# precharge.net
KiCad netlist of a schematic drawn in EAGLE
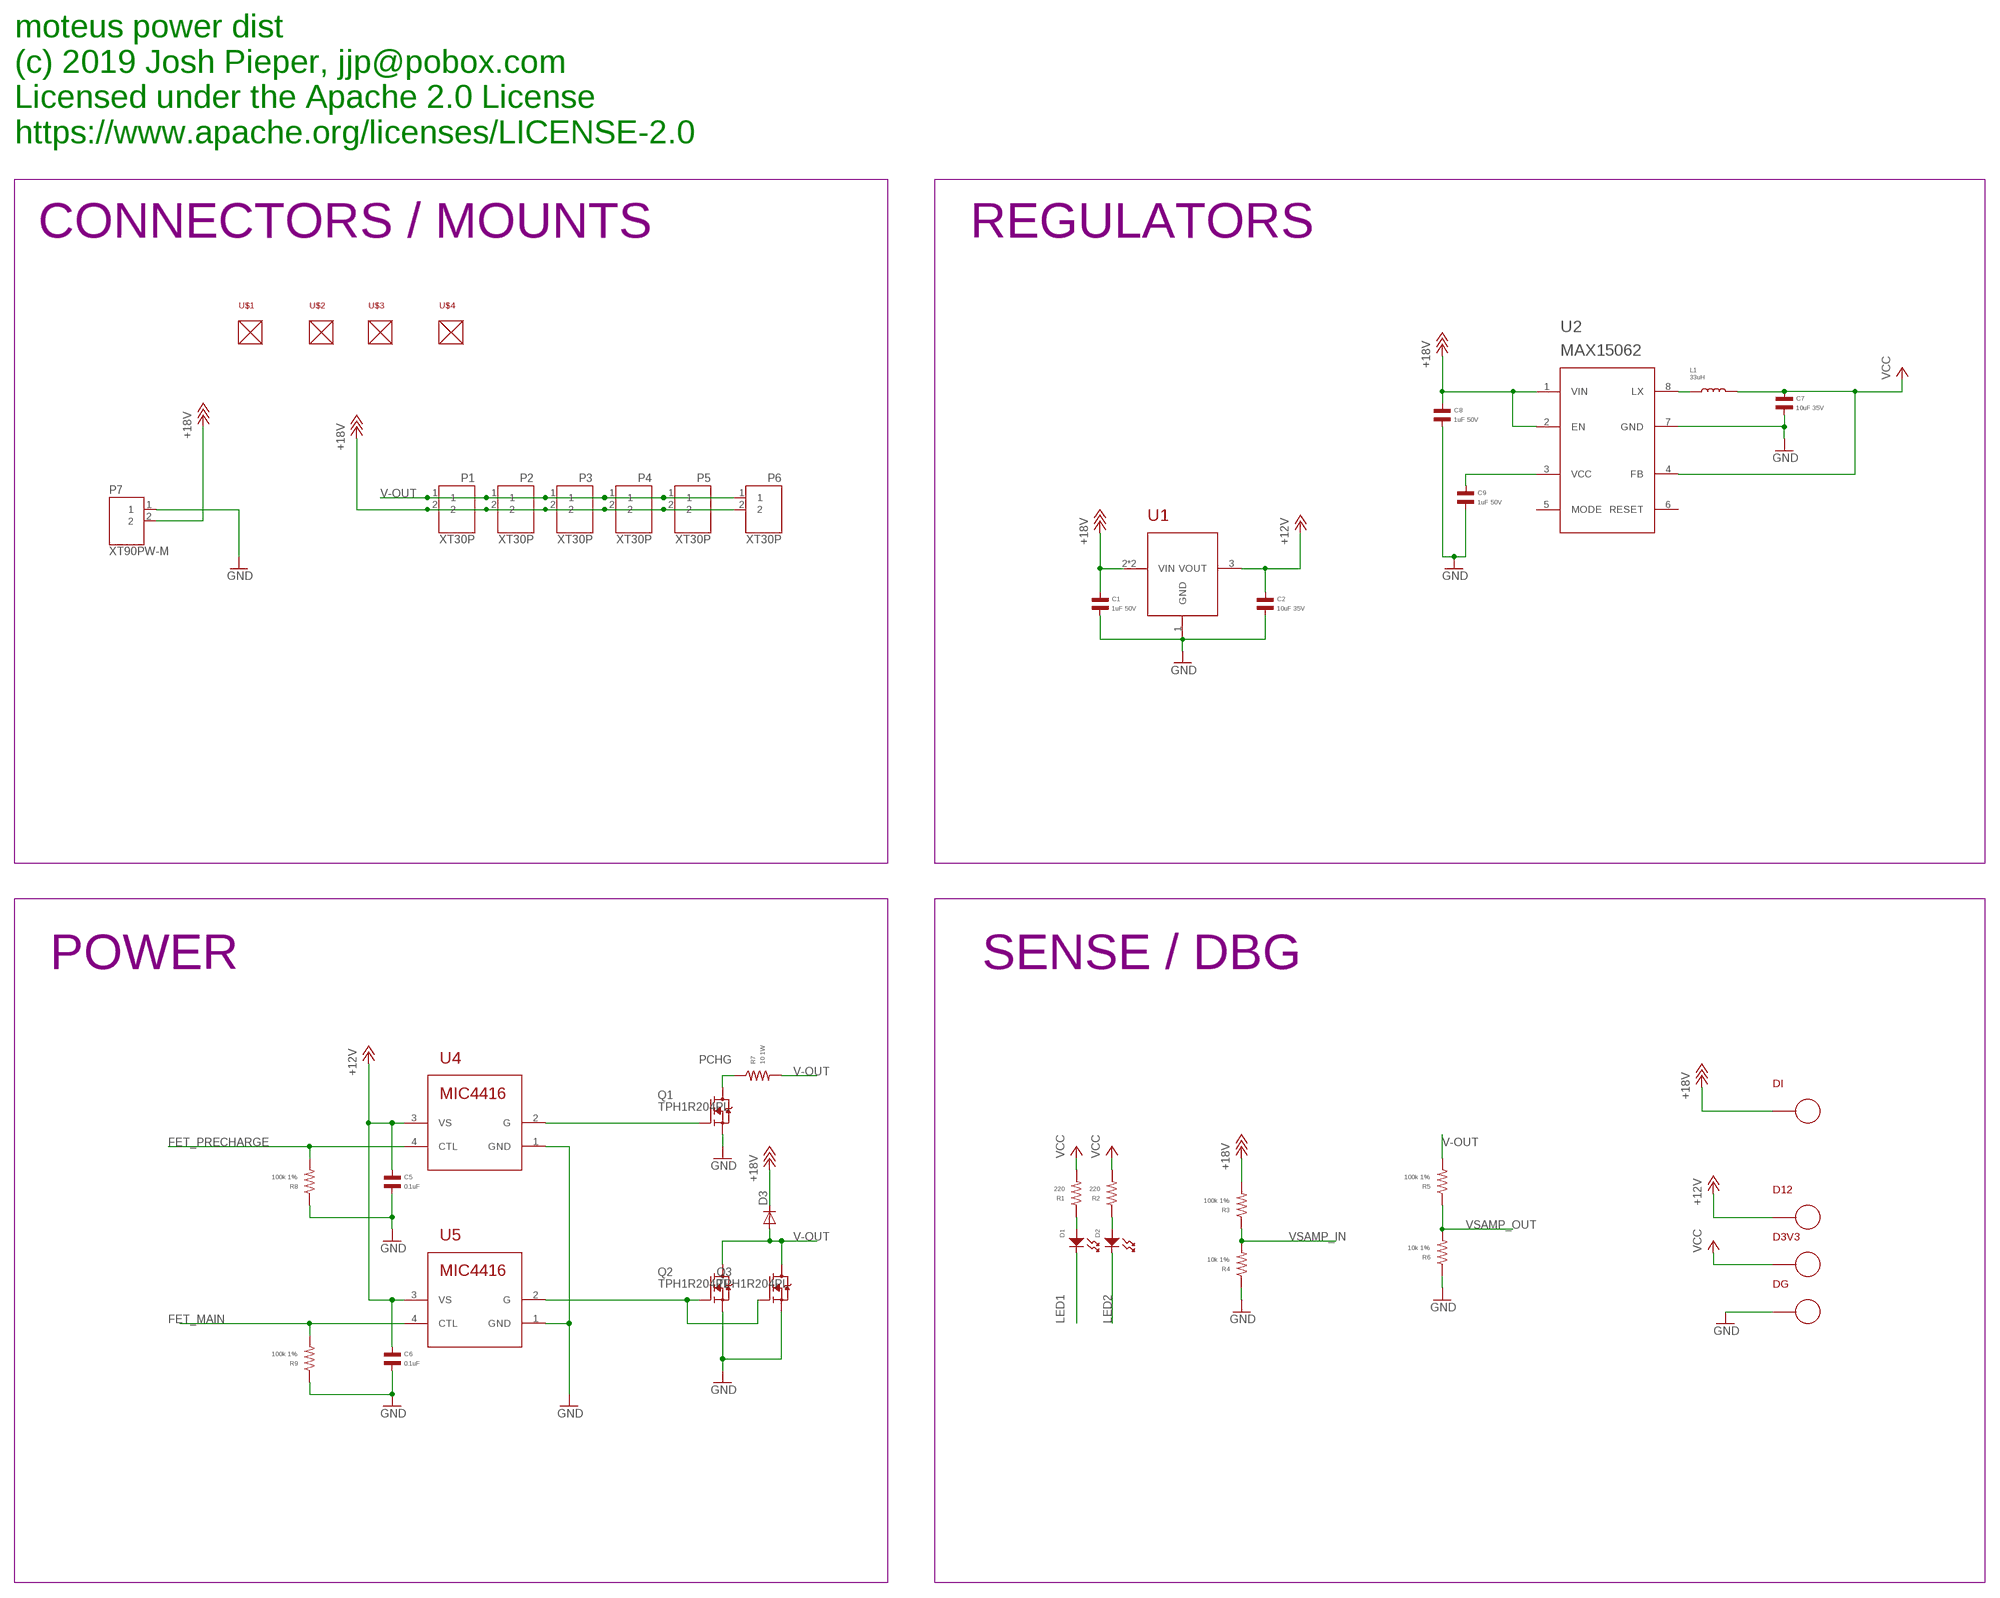
[diagram p0: schematic, sheet 1, part 1 of 2]
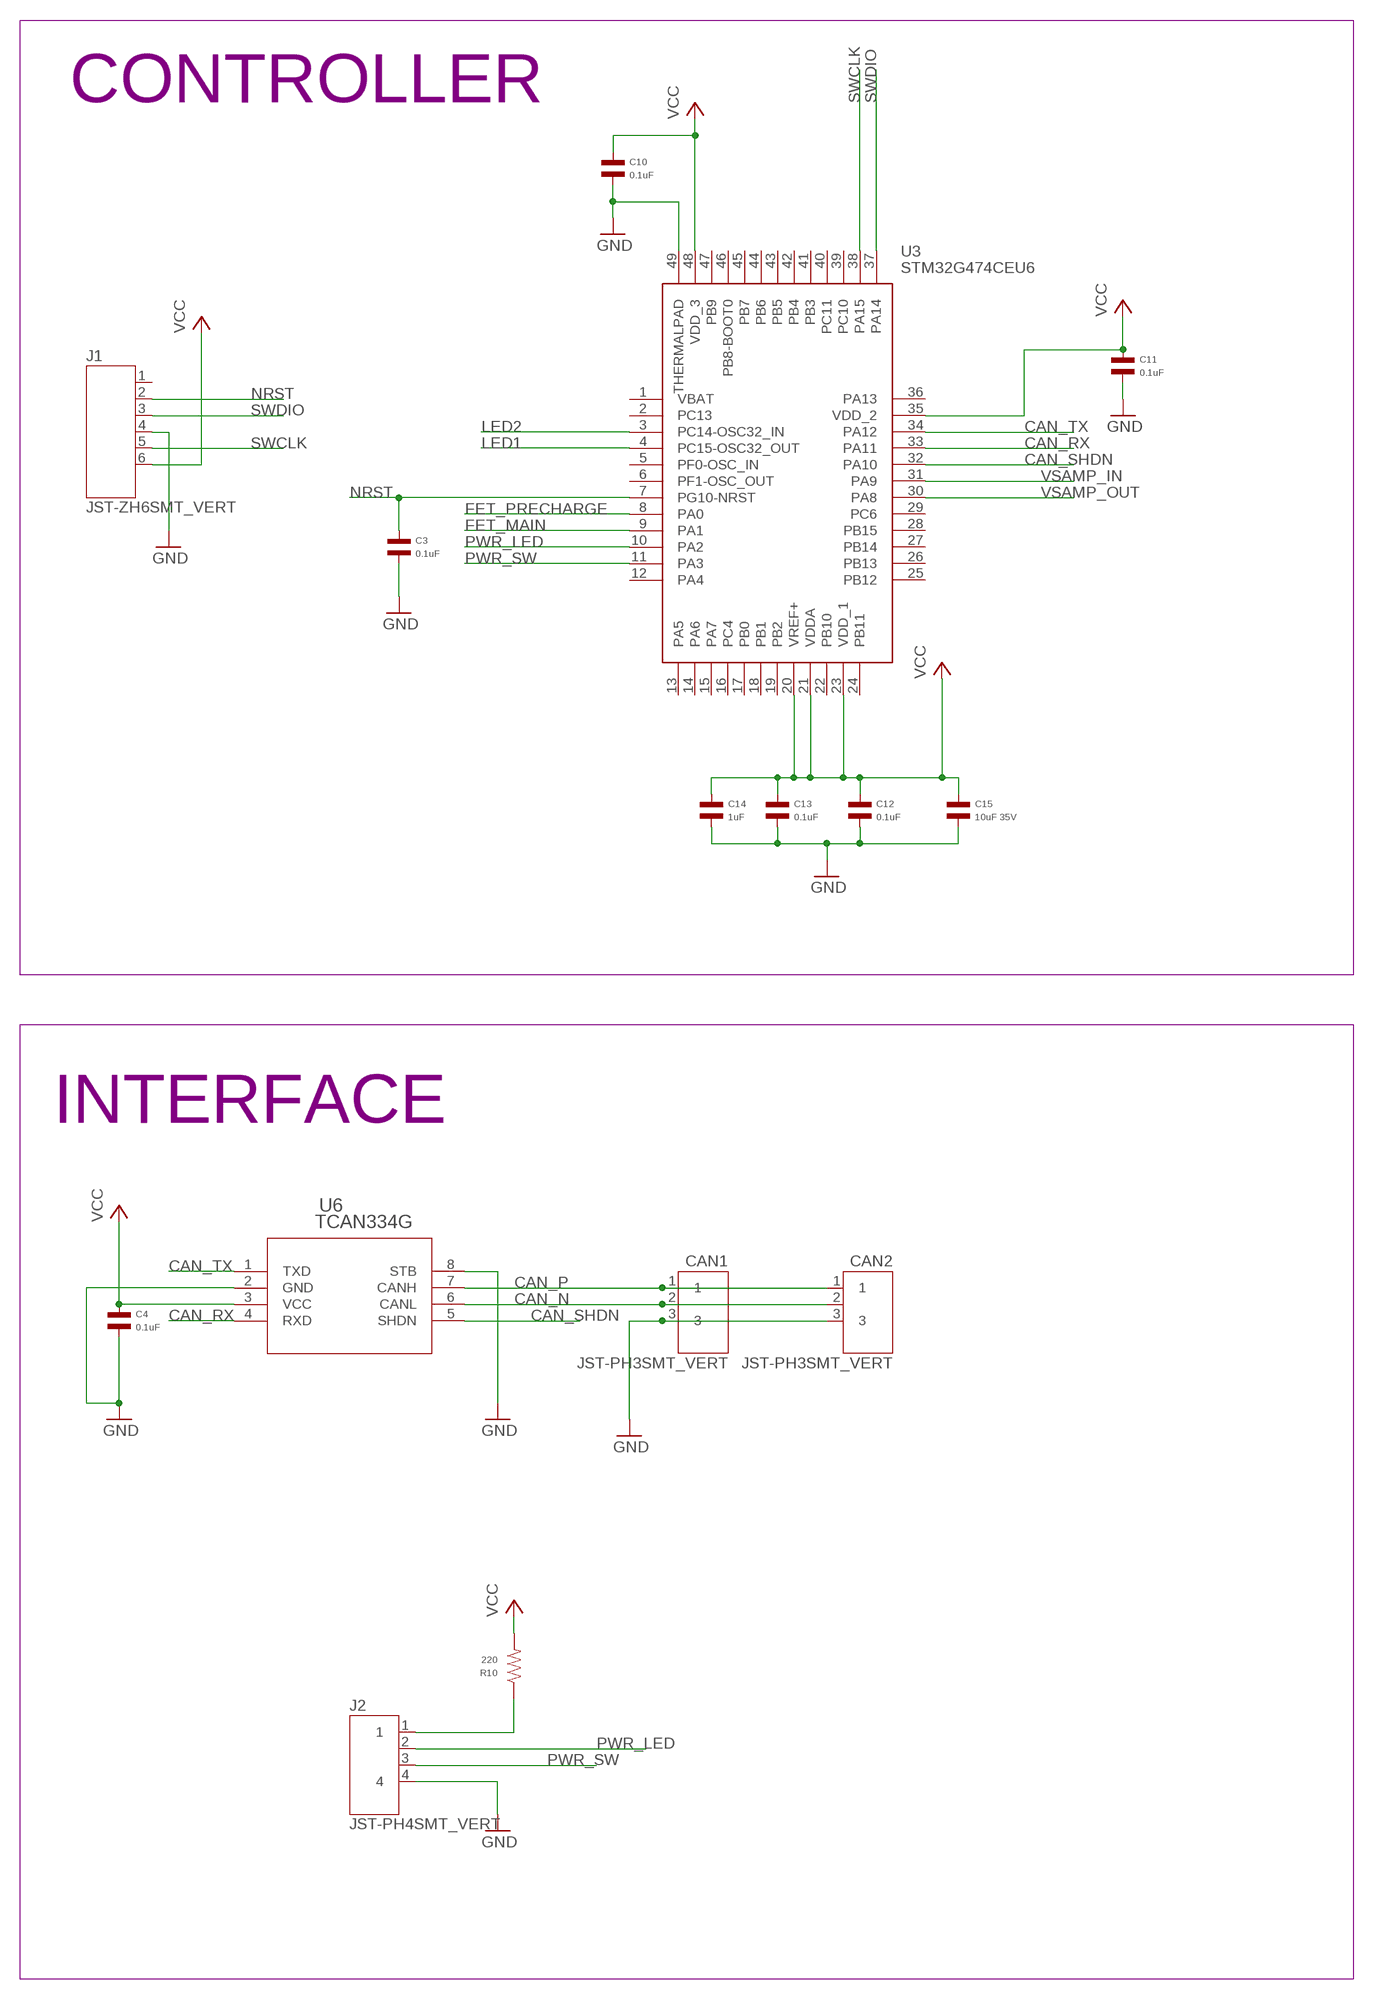
[diagram p1: schematic, sheet 1, part 2 of 2]

(export (version "E")
  (design (tool "Eeschema 10.0.6"))
  (components
    (comp (ref "C1")
      (value "1uF 50V")
      (footprint "eagle-import:C0603")
      (fields (field (name "MF") "SAMSUNG") (field (name "MPN") "CL10A105KB8NNNC"))
      (libsource (lib "eagle-import") (part "CAPACITOR_NP_0603"))
    )
    (comp (ref "C2")
      (value "10uF 35V")
      (footprint "eagle-import:C1206")
      (fields (field (name "MF") "TDK") (field (name "MPN") "CGA5L1X7R1V106K160AC"))
      (libsource (lib "eagle-import") (part "CAPACITOR_NP_1206"))
    )
    (comp (ref "C3")
      (value "0.1uF")
      (footprint "eagle-import:C0402")
      (fields (field (name "HOUSEPART") "1") (field (name "MPN") "MF-CAP-0402-0.1uF"))
      (libsource (lib "eagle-import") (part "CAPACITOR_NP_0402"))
    )
    (comp (ref "C4")
      (value "0.1uF")
      (footprint "eagle-import:C0402")
      (fields (field (name "HOUSEPART") "1") (field (name "MPN") "MF-CAP-0402-0.1uF"))
      (libsource (lib "eagle-import") (part "CAPACITOR_NP_0402"))
    )
    (comp (ref "C5")
      (value "0.1uF")
      (footprint "eagle-import:C0402")
      (fields (field (name "HOUSEPART") "1") (field (name "MPN") "MF-CAP-0402-0.1uF"))
      (libsource (lib "eagle-import") (part "CAPACITOR_NP_0402"))
    )
    (comp (ref "C6")
      (value "0.1uF")
      (footprint "eagle-import:C0402")
      (fields (field (name "HOUSEPART") "1") (field (name "MPN") "MF-CAP-0402-0.1uF"))
      (libsource (lib "eagle-import") (part "CAPACITOR_NP_0402"))
    )
    (comp (ref "C7")
      (value "10uF 35V")
      (footprint "eagle-import:C1206")
      (fields (field (name "MF") "TDK") (field (name "MPN") "CGA5L1X7R1V106K160AC"))
      (libsource (lib "eagle-import") (part "CAPACITOR_NP_1206"))
    )
    (comp (ref "C8")
      (value "1uF 50V")
      (footprint "eagle-import:C0603")
      (fields (field (name "MF") "SAMSUNG") (field (name "MPN") "CL10A105KB8NNNC"))
      (libsource (lib "eagle-import") (part "CAPACITOR_NP_0603"))
    )
    (comp (ref "C9")
      (value "1uF 50V")
      (footprint "eagle-import:C0603")
      (fields (field (name "MF") "SAMSUNG") (field (name "MPN") "CL10A105KB8NNNC"))
      (libsource (lib "eagle-import") (part "CAPACITOR_NP_0603"))
    )
    (comp (ref "C10")
      (value "0.1uF")
      (footprint "eagle-import:C0402")
      (fields (field (name "HOUSEPART") "1") (field (name "MPN") "MF-CAP-0402-0.1uF"))
      (libsource (lib "eagle-import") (part "CAPACITOR_NP_0402"))
    )
    (comp (ref "C11")
      (value "0.1uF")
      (footprint "eagle-import:C0402")
      (fields (field (name "HOUSEPART") "1") (field (name "MPN") "MF-CAP-0402-0.1uF"))
      (libsource (lib "eagle-import") (part "CAPACITOR_NP_0402"))
    )
    (comp (ref "C12")
      (value "0.1uF")
      (footprint "eagle-import:C0402")
      (fields (field (name "HOUSEPART") "1") (field (name "MPN") "MF-CAP-0402-0.1uF"))
      (libsource (lib "eagle-import") (part "CAPACITOR_NP_0402"))
    )
    (comp (ref "C13")
      (value "0.1uF")
      (footprint "eagle-import:C0402")
      (fields (field (name "HOUSEPART") "1") (field (name "MPN") "MF-CAP-0402-0.1uF"))
      (libsource (lib "eagle-import") (part "CAPACITOR_NP_0402"))
    )
    (comp (ref "C14")
      (value "1uF")
      (footprint "eagle-import:C0402")
      (fields (field (name "HOUSEPART") "1") (field (name "MPN") "MF-CAP-0402-1uF"))
      (libsource (lib "eagle-import") (part "CAPACITOR_NP_0402"))
    )
    (comp (ref "C15")
      (value "10uF 35V")
      (footprint "eagle-import:C1206")
      (fields (field (name "MF") "TDK") (field (name "MPN") "CGA5L1X7R1V106K160AC"))
      (libsource (lib "eagle-import") (part "CAPACITOR_NP_1206"))
    )
    (comp (ref "CAN1")
      (value "JST-PH3SMT_VERT")
      (footprint "eagle-import:JST_B3B_PH-SM4-TB(LF)(SN)")
      (fields (field (name "MF") "JST") (field (name "MPN") "B3B-PH-SM4-TB(LF)(SN)"))
      (libsource (lib "eagle-import") (part "JST-PH3SMT_VERT"))
    )
    (comp (ref "CAN2")
      (value "JST-PH3SMT_VERT")
      (footprint "eagle-import:JST_B3B_PH-SM4-TB(LF)(SN)")
      (fields (field (name "MF") "JST") (field (name "MPN") "B3B-PH-SM4-TB(LF)(SN)"))
      (libsource (lib "eagle-import") (part "JST-PH3SMT_VERT"))
    )
    (comp (ref "D1")
      (value "LED_SINGLE-0603")
      (footprint "eagle-import:LED0603")
      (fields
        (field (name "HOUSEPART") "NO")
        (field (name "HOUSEPART_1") "1")
        (field (name "MPN") "MF-LED-0603-RED")
      )
      (libsource (lib "eagle-import") (part "LED_SINGLE-0603"))
    )
    (comp (ref "D2")
      (value "LED_SINGLE-0603")
      (footprint "eagle-import:LED0603")
      (fields
        (field (name "HOUSEPART") "NO")
        (field (name "HOUSEPART_1") "1")
        (field (name "MPN") "MF-LED-0603-RED")
      )
      (libsource (lib "eagle-import") (part "LED_SINGLE-0603"))
    )
    (comp (ref "D3")
      (value "DIODE-")
      (footprint "eagle-import:DO-214AB")
      (fields (field (name "MF") "MICRO COMMERCIAL") (field (name "MPN") "SK510L-TP"))
      (libsource (lib "eagle-import") (part "DIODE-"))
    )
    (comp (ref "D3V3")
      (value "PAD24AWG_PAD")
      (footprint "eagle-import:24AWG_PAD")
      (libsource (lib "eagle-import") (part "PAD24AWG_PAD"))
    )
    (comp (ref "D12")
      (value "PAD24AWG_PAD")
      (footprint "eagle-import:24AWG_PAD")
      (libsource (lib "eagle-import") (part "PAD24AWG_PAD"))
    )
    (comp (ref "DG")
      (value "PAD24AWG_PAD")
      (footprint "eagle-import:24AWG_PAD")
      (libsource (lib "eagle-import") (part "PAD24AWG_PAD"))
    )
    (comp (ref "DI")
      (value "PAD24AWG_PAD")
      (footprint "eagle-import:24AWG_PAD")
      (libsource (lib "eagle-import") (part "PAD24AWG_PAD"))
    )
    (comp (ref "J1")
      (value "JST-ZH6SMT_VERT")
      (footprint "eagle-import:JST_B6B-ZR-SM4-TF(LF)(SN)")
      (fields (field (name "MF") "JST") (field (name "MPN") "B6B-ZR-SM4-TF(LF)(SN)"))
      (libsource (lib "eagle-import") (part "JST-ZH6SMT_VERT"))
    )
    (comp (ref "J2")
      (value "JST-PH4SMT_VERT")
      (footprint "eagle-import:JST_B4B_PH-SM4-TB(LF)(SN)")
      (fields (field (name "MF") "JST") (field (name "MPN") "B4B-PH-SM4-TB(LF)(SN)"))
      (libsource (lib "eagle-import") (part "JST-PH4SMT_VERT"))
    )
    (comp (ref "L1")
      (value "33uH")
      (footprint "eagle-import:L1210")
      (fields (field (name "MF") "TDK") (field (name "MPN") "NLFV32T-330K-EF") (field (name "POPULATE") "1"))
      (libsource (lib "eagle-import") (part "INDUCTOR_1210"))
    )
    (comp (ref "P1")
      (value "XT30P")
      (footprint "eagle-import:XT30P")
      (libsource (lib "eagle-import") (part "XT30P"))
    )
    (comp (ref "P2")
      (value "XT30P")
      (footprint "eagle-import:XT30P")
      (libsource (lib "eagle-import") (part "XT30P"))
    )
    (comp (ref "P3")
      (value "XT30P")
      (footprint "eagle-import:XT30P")
      (libsource (lib "eagle-import") (part "XT30P"))
    )
    (comp (ref "P4")
      (value "XT30P")
      (footprint "eagle-import:XT30P")
      (libsource (lib "eagle-import") (part "XT30P"))
    )
    (comp (ref "P5")
      (value "XT30P")
      (footprint "eagle-import:XT30P")
      (libsource (lib "eagle-import") (part "XT30P"))
    )
    (comp (ref "P6")
      (value "XT30P")
      (footprint "eagle-import:XT30P")
      (libsource (lib "eagle-import") (part "XT30P"))
    )
    (comp (ref "P7")
      (value "XT90PW-M")
      (footprint "eagle-import:XT90PW-M")
      (libsource (lib "eagle-import") (part "XT90PW-M"))
    )
    (comp (ref "Q1")
      (value "TPH1R204PL")
      (footprint "eagle-import:SOP_ADVANCE")
      (fields (field (name "MF") "Toshiba") (field (name "MPN") "TPH1R204PL,L1Q"))
      (libsource (lib "eagle-import") (part "TPH1R204PL"))
    )
    (comp (ref "Q2")
      (value "TPH1R204PL")
      (footprint "eagle-import:SOP_ADVANCE")
      (fields (field (name "MF") "Toshiba") (field (name "MPN") "TPH1R204PL,L1Q"))
      (libsource (lib "eagle-import") (part "TPH1R204PL"))
    )
    (comp (ref "Q3")
      (value "TPH1R204PL")
      (footprint "eagle-import:SOP_ADVANCE")
      (fields (field (name "MF") "Toshiba") (field (name "MPN") "TPH1R204PL,L1Q"))
      (libsource (lib "eagle-import") (part "TPH1R204PL"))
    )
    (comp (ref "R1")
      (value "220")
      (footprint "eagle-import:R0603")
      (fields (field (name "HOUSEPART") "1") (field (name "MPN") "MF-RES-0603-220"))
      (libsource (lib "eagle-import") (part "RESISTOR_0603"))
    )
    (comp (ref "R2")
      (value "220")
      (footprint "eagle-import:R0603")
      (fields (field (name "HOUSEPART") "1") (field (name "MPN") "MF-RES-0603-220"))
      (libsource (lib "eagle-import") (part "RESISTOR_0603"))
    )
    (comp (ref "R3")
      (value "100k 1%")
      (footprint "eagle-import:R0603")
      (fields (field (name "MF") "VISHAY") (field (name "MPN") "CRCW0603100KFKEA"))
      (libsource (lib "eagle-import") (part "RESISTOR_0603"))
    )
    (comp (ref "R4")
      (value "10k 1%")
      (footprint "eagle-import:R0603")
      (fields (field (name "MF") "PANASONIC") (field (name "MPN") "P10.0KHDKR-ND"))
      (libsource (lib "eagle-import") (part "RESISTOR_0603"))
    )
    (comp (ref "R5")
      (value "100k 1%")
      (footprint "eagle-import:R0603")
      (fields (field (name "MF") "VISHAY") (field (name "MPN") "CRCW0603100KFKEA"))
      (libsource (lib "eagle-import") (part "RESISTOR_0603"))
    )
    (comp (ref "R6")
      (value "10k 1%")
      (footprint "eagle-import:R0603")
      (fields (field (name "MF") "PANASONIC") (field (name "MPN") "P10.0KHDKR-ND"))
      (libsource (lib "eagle-import") (part "RESISTOR_0603"))
    )
    (comp (ref "R7")
      (value "10 1W")
      (footprint "eagle-import:R1206")
      (fields (field (name "MF") "Susumu") (field (name "MPN") "HRG3216Q-10R0-D-T1"))
      (libsource (lib "eagle-import") (part "RESISTOR_1206"))
    )
    (comp (ref "R8")
      (value "100k 1%")
      (footprint "eagle-import:R0603")
      (fields (field (name "MF") "VISHAY") (field (name "MPN") "CRCW0603100KFKEA"))
      (libsource (lib "eagle-import") (part "RESISTOR_0603"))
    )
    (comp (ref "R9")
      (value "100k 1%")
      (footprint "eagle-import:R0603")
      (fields (field (name "MF") "VISHAY") (field (name "MPN") "CRCW0603100KFKEA"))
      (libsource (lib "eagle-import") (part "RESISTOR_0603"))
    )
    (comp (ref "R10")
      (value "220")
      (footprint "eagle-import:R0603")
      (fields (field (name "HOUSEPART") "1") (field (name "MPN") "MF-RES-0603-220"))
      (libsource (lib "eagle-import") (part "RESISTOR_0603"))
    )
    (comp (ref "U$1")
      (value "MOUNT")
      (footprint "eagle-import:M2.5MOUNT")
      (libsource (lib "eagle-import") (part "MOUNT"))
    )
    (comp (ref "U$2")
      (value "MOUNT")
      (footprint "eagle-import:M2.5MOUNT")
      (libsource (lib "eagle-import") (part "MOUNT"))
    )
    (comp (ref "U$3")
      (value "MOUNT")
      (footprint "eagle-import:M2.5MOUNT")
      (libsource (lib "eagle-import") (part "MOUNT"))
    )
    (comp (ref "U$4")
      (value "MOUNT")
      (footprint "eagle-import:M2.5MOUNT")
      (libsource (lib "eagle-import") (part "MOUNT"))
    )
    (comp (ref "U1")
      (value "ZXTR2012Z")
      (footprint "eagle-import:SOT89")
      (fields (field (name "MF") "DIODES INC") (field (name "MPN") "ZXTR2012Z-13"))
      (libsource (lib "eagle-import") (part "ZXTR2012Z"))
    )
    (comp (ref "U2")
      (value "MAX150628TDFN")
      (footprint "eagle-import:8TDFN")
      (fields (field (name "MF") "MAXIM") (field (name "MPN") "MAX15062AATA+T"))
      (libsource (lib "eagle-import") (part "MAX150628TDFN"))
    )
    (comp (ref "U3")
      (value "STM32G474CEU6")
      (footprint "eagle-import:QFN50P700X700X60-49N")
      (fields (field (name "MOUSER_PART_NUMBER") "511-STM32G474CEU6") (field (name "MF") "ST"))
      (libsource (lib "eagle-import") (part "STM32G474CEU6"))
    )
    (comp (ref "U4")
      (value "MIC4416")
      (footprint "eagle-import:SOT143")
      (fields (field (name "MF") "MICROCHIP") (field (name "MPN") "MIC4416YM4-TR"))
      (libsource (lib "eagle-import") (part "MIC4416"))
    )
    (comp (ref "U5")
      (value "MIC4416")
      (footprint "eagle-import:SOT143")
      (fields (field (name "MF") "MICROCHIP") (field (name "MPN") "MIC4416YM4-TR"))
      (libsource (lib "eagle-import") (part "MIC4416"))
    )
    (comp (ref "U6")
      (value "TCAN334G")
      (footprint "eagle-import:SOIC8")
      (fields (field (name "MF") "TI") (field (name "MPN") "TCAN334GDR"))
      (libsource (lib "eagle-import") (part "TCAN334G"))
    )
  )
  (nets
    (net (code "1") (name "+12V") (class "Default")
      (node (ref "C2") (pin "P$1") (pinfunction "P$1_P$1") (pintype "passive"))
      (node (ref "C5") (pin "P$1") (pinfunction "P$1_P$1") (pintype "passive"))
      (node (ref "C6") (pin "P$1") (pinfunction "P$1_P$1") (pintype "passive"))
      (node (ref "D12") (pin "P$1") (pinfunction "P$1_P$1") (pintype "bidirectional"))
      (node (ref "U1") (pin "3") (pinfunction "VOUT_3") (pintype "bidirectional"))
      (node (ref "U4") (pin "3") (pinfunction "VS_3") (pintype "bidirectional"))
      (node (ref "U5") (pin "3") (pinfunction "VS_3") (pintype "bidirectional"))
    )
    (net (code "2") (name "+18V") (class "Default")
      (node (ref "C1") (pin "P$1") (pinfunction "P$1_P$1") (pintype "passive"))
      (node (ref "C8") (pin "P$1") (pinfunction "P$1_P$1") (pintype "passive"))
      (node (ref "D3") (pin "C") (pinfunction "C_C") (pintype "passive"))
      (node (ref "DI") (pin "P$1") (pinfunction "P$1_P$1") (pintype "bidirectional"))
      (node (ref "P1") (pin "2") (pinfunction "2_2") (pintype "passive"))
      (node (ref "P2") (pin "2") (pinfunction "2_2") (pintype "passive"))
      (node (ref "P3") (pin "2") (pinfunction "2_2") (pintype "passive"))
      (node (ref "P4") (pin "2") (pinfunction "2_2") (pintype "passive"))
      (node (ref "P5") (pin "2") (pinfunction "2_2") (pintype "passive"))
      (node (ref "P6") (pin "2") (pinfunction "2_2") (pintype "passive"))
      (node (ref "P7") (pin "2") (pinfunction "2_2") (pintype "passive"))
      (node (ref "R3") (pin "P$2") (pinfunction "P$2_P$2") (pintype "passive"))
      (node (ref "U1") (pin "2") (pinfunction "VIN_2") (pintype "bidirectional"))
      (node (ref "U1") (pin "PAD") (pinfunction "VIN_PAD") (pintype "bidirectional"))
      (node (ref "U2") (pin "1") (pinfunction "VIN_1") (pintype "passive"))
      (node (ref "U2") (pin "2") (pinfunction "EN_2") (pintype "passive"))
    )
    (net (code "3") (name "/CAN_N") (class "Default")
      (node (ref "CAN1") (pin "2") (pinfunction "2_2") (pintype "passive"))
      (node (ref "CAN2") (pin "2") (pinfunction "2_2") (pintype "passive"))
      (node (ref "U6") (pin "6") (pinfunction "CANL_6") (pintype "bidirectional"))
    )
    (net (code "4") (name "/CAN_P") (class "Default")
      (node (ref "CAN1") (pin "1") (pinfunction "1_1") (pintype "passive"))
      (node (ref "CAN2") (pin "1") (pinfunction "1_1") (pintype "passive"))
      (node (ref "U6") (pin "7") (pinfunction "CANH_7") (pintype "bidirectional"))
    )
    (net (code "5") (name "/CAN_RX") (class "Default")
      (node (ref "U3") (pin "33") (pinfunction "PA11_33") (pintype "bidirectional"))
      (node (ref "U6") (pin "4") (pinfunction "RXD_4") (pintype "output"))
    )
    (net (code "6") (name "/CAN_SHDN") (class "Default")
      (node (ref "U3") (pin "32") (pinfunction "PA10_32") (pintype "bidirectional"))
      (node (ref "U6") (pin "5") (pinfunction "SHDN_5") (pintype "input"))
    )
    (net (code "7") (name "/CAN_TX") (class "Default")
      (node (ref "U3") (pin "34") (pinfunction "PA12_34") (pintype "bidirectional"))
      (node (ref "U6") (pin "1") (pinfunction "TXD_1") (pintype "input"))
    )
    (net (code "8") (name "/FET_MAIN") (class "Default")
      (node (ref "R9") (pin "P$2") (pinfunction "P$2_P$2") (pintype "passive"))
      (node (ref "U3") (pin "9") (pinfunction "PA1_9") (pintype "bidirectional"))
      (node (ref "U5") (pin "4") (pinfunction "CTL_4") (pintype "bidirectional"))
    )
    (net (code "9") (name "/FET_PRECHARGE") (class "Default")
      (node (ref "R8") (pin "P$2") (pinfunction "P$2_P$2") (pintype "passive"))
      (node (ref "U3") (pin "8") (pinfunction "PA0_8") (pintype "bidirectional"))
      (node (ref "U4") (pin "4") (pinfunction "CTL_4") (pintype "bidirectional"))
    )
    (net (code "10") (name "/LED1") (class "Default")
      (node (ref "D1") (pin "CATHODE") (pinfunction "CATHODE_CATHODE") (pintype "power_in"))
      (node (ref "U3") (pin "4") (pinfunction "PC15-OSC32_OUT_4") (pintype "bidirectional"))
    )
    (net (code "11") (name "/LED2") (class "Default")
      (node (ref "D2") (pin "CATHODE") (pinfunction "CATHODE_CATHODE") (pintype "power_in"))
      (node (ref "U3") (pin "3") (pinfunction "PC14-OSC32_IN_3") (pintype "bidirectional"))
    )
    (net (code "12") (name "/NRST") (class "Default")
      (node (ref "C3") (pin "P$1") (pinfunction "P$1_P$1") (pintype "passive"))
      (node (ref "J1") (pin "2") (pinfunction "2_2") (pintype "passive"))
      (node (ref "U3") (pin "7") (pinfunction "PG10-NRST_7") (pintype "bidirectional"))
    )
    (net (code "13") (name "/PCHG") (class "Default")
      (node (ref "Q1") (pin "5") (pinfunction "D_5") (pintype "passive"))
      (node (ref "Q1") (pin "6") (pinfunction "D_6") (pintype "passive"))
      (node (ref "Q1") (pin "7") (pinfunction "D_7") (pintype "passive"))
      (node (ref "Q1") (pin "8") (pinfunction "D_8") (pintype "passive"))
      (node (ref "Q1") (pin "PAD") (pinfunction "D_PAD") (pintype "passive"))
      (node (ref "R7") (pin "P$1") (pinfunction "P$1_P$1") (pintype "passive"))
    )
    (net (code "14") (name "/PWR_LED") (class "Default")
      (node (ref "J2") (pin "2") (pinfunction "2_2") (pintype "passive"))
      (node (ref "U3") (pin "10") (pinfunction "PA2_10") (pintype "bidirectional"))
    )
    (net (code "15") (name "/PWR_SW") (class "Default")
      (node (ref "J2") (pin "3") (pinfunction "3_3") (pintype "passive"))
      (node (ref "U3") (pin "11") (pinfunction "PA3_11") (pintype "bidirectional"))
    )
    (net (code "16") (name "/SWCLK") (class "Default")
      (node (ref "J1") (pin "5") (pinfunction "5_5") (pintype "passive"))
      (node (ref "U3") (pin "38") (pinfunction "PA15_38") (pintype "bidirectional"))
    )
    (net (code "17") (name "/SWDIO") (class "Default")
      (node (ref "J1") (pin "3") (pinfunction "3_3") (pintype "passive"))
      (node (ref "U3") (pin "37") (pinfunction "PA14_37") (pintype "bidirectional"))
    )
    (net (code "18") (name "/V-OUT") (class "Default")
      (node (ref "D3") (pin "A") (pinfunction "A_A") (pintype "passive"))
      (node (ref "P1") (pin "1") (pinfunction "1_1") (pintype "passive"))
      (node (ref "P2") (pin "1") (pinfunction "1_1") (pintype "passive"))
      (node (ref "P3") (pin "1") (pinfunction "1_1") (pintype "passive"))
      (node (ref "P4") (pin "1") (pinfunction "1_1") (pintype "passive"))
      (node (ref "P5") (pin "1") (pinfunction "1_1") (pintype "passive"))
      (node (ref "P6") (pin "1") (pinfunction "1_1") (pintype "passive"))
      (node (ref "Q2") (pin "5") (pinfunction "D_5") (pintype "passive"))
      (node (ref "Q2") (pin "6") (pinfunction "D_6") (pintype "passive"))
      (node (ref "Q2") (pin "7") (pinfunction "D_7") (pintype "passive"))
      (node (ref "Q2") (pin "8") (pinfunction "D_8") (pintype "passive"))
      (node (ref "Q2") (pin "PAD") (pinfunction "D_PAD") (pintype "passive"))
      (node (ref "Q3") (pin "5") (pinfunction "D_5") (pintype "passive"))
      (node (ref "Q3") (pin "6") (pinfunction "D_6") (pintype "passive"))
      (node (ref "Q3") (pin "7") (pinfunction "D_7") (pintype "passive"))
      (node (ref "Q3") (pin "8") (pinfunction "D_8") (pintype "passive"))
      (node (ref "Q3") (pin "PAD") (pinfunction "D_PAD") (pintype "passive"))
      (node (ref "R5") (pin "P$2") (pinfunction "P$2_P$2") (pintype "passive"))
      (node (ref "R7") (pin "P$2") (pinfunction "P$2_P$2") (pintype "passive"))
    )
    (net (code "19") (name "/VSAMP_IN") (class "Default")
      (node (ref "R3") (pin "P$1") (pinfunction "P$1_P$1") (pintype "passive"))
      (node (ref "R4") (pin "P$2") (pinfunction "P$2_P$2") (pintype "passive"))
      (node (ref "U3") (pin "31") (pinfunction "PA9_31") (pintype "bidirectional"))
    )
    (net (code "20") (name "/VSAMP_OUT") (class "Default")
      (node (ref "R5") (pin "P$1") (pinfunction "P$1_P$1") (pintype "passive"))
      (node (ref "R6") (pin "P$2") (pinfunction "P$2_P$2") (pintype "passive"))
      (node (ref "U3") (pin "30") (pinfunction "PA8_30") (pintype "bidirectional"))
    )
    (net (code "21") (name "GND") (class "Default")
      (node (ref "C1") (pin "P$2") (pinfunction "P$2_P$2") (pintype "passive"))
      (node (ref "C10") (pin "P$2") (pinfunction "P$2_P$2") (pintype "passive"))
      (node (ref "C11") (pin "P$2") (pinfunction "P$2_P$2") (pintype "passive"))
      (node (ref "C12") (pin "P$2") (pinfunction "P$2_P$2") (pintype "passive"))
      (node (ref "C13") (pin "P$2") (pinfunction "P$2_P$2") (pintype "passive"))
      (node (ref "C14") (pin "P$2") (pinfunction "P$2_P$2") (pintype "passive"))
      (node (ref "C15") (pin "P$2") (pinfunction "P$2_P$2") (pintype "passive"))
      (node (ref "C2") (pin "P$2") (pinfunction "P$2_P$2") (pintype "passive"))
      (node (ref "C3") (pin "P$2") (pinfunction "P$2_P$2") (pintype "passive"))
      (node (ref "C4") (pin "P$2") (pinfunction "P$2_P$2") (pintype "passive"))
      (node (ref "C5") (pin "P$2") (pinfunction "P$2_P$2") (pintype "passive"))
      (node (ref "C6") (pin "P$2") (pinfunction "P$2_P$2") (pintype "passive"))
      (node (ref "C7") (pin "P$2") (pinfunction "P$2_P$2") (pintype "passive"))
      (node (ref "C8") (pin "P$2") (pinfunction "P$2_P$2") (pintype "passive"))
      (node (ref "C9") (pin "P$2") (pinfunction "P$2_P$2") (pintype "passive"))
      (node (ref "CAN1") (pin "3") (pinfunction "3_3") (pintype "passive"))
      (node (ref "CAN2") (pin "3") (pinfunction "3_3") (pintype "passive"))
      (node (ref "DG") (pin "P$1") (pinfunction "P$1_P$1") (pintype "bidirectional"))
      (node (ref "J1") (pin "4") (pinfunction "4_4") (pintype "passive"))
      (node (ref "J2") (pin "4") (pinfunction "4_4") (pintype "passive"))
      (node (ref "P7") (pin "1") (pinfunction "1_1") (pintype "passive"))
      (node (ref "Q1") (pin "1") (pinfunction "S_1") (pintype "passive"))
      (node (ref "Q1") (pin "2") (pinfunction "S_2") (pintype "passive"))
      (node (ref "Q1") (pin "3") (pinfunction "S_3") (pintype "passive"))
      (node (ref "Q2") (pin "1") (pinfunction "S_1") (pintype "passive"))
      (node (ref "Q2") (pin "2") (pinfunction "S_2") (pintype "passive"))
      (node (ref "Q2") (pin "3") (pinfunction "S_3") (pintype "passive"))
      (node (ref "Q3") (pin "1") (pinfunction "S_1") (pintype "passive"))
      (node (ref "Q3") (pin "2") (pinfunction "S_2") (pintype "passive"))
      (node (ref "Q3") (pin "3") (pinfunction "S_3") (pintype "passive"))
      (node (ref "R4") (pin "P$1") (pinfunction "P$1_P$1") (pintype "passive"))
      (node (ref "R6") (pin "P$1") (pinfunction "P$1_P$1") (pintype "passive"))
      (node (ref "R8") (pin "P$1") (pinfunction "P$1_P$1") (pintype "passive"))
      (node (ref "R9") (pin "P$1") (pinfunction "P$1_P$1") (pintype "passive"))
      (node (ref "U1") (pin "1") (pinfunction "GND_1") (pintype "bidirectional"))
      (node (ref "U2") (pin "7") (pinfunction "GND_7") (pintype "passive"))
      (node (ref "U3") (pin "49") (pinfunction "THERMALPAD_49") (pintype "bidirectional"))
      (node (ref "U4") (pin "1") (pinfunction "GND_1") (pintype "bidirectional"))
      (node (ref "U5") (pin "1") (pinfunction "GND_1") (pintype "bidirectional"))
      (node (ref "U6") (pin "2") (pinfunction "GND_2") (pintype "power_in"))
      (node (ref "U6") (pin "8") (pinfunction "STB_8") (pintype "input"))
    )
    (net (code "22") (name "Net-(D1-PadANODE)") (class "Default")
      (node (ref "D1") (pin "ANODE") (pinfunction "ANODE_ANODE") (pintype "power_in"))
      (node (ref "R1") (pin "P$1") (pinfunction "P$1_P$1") (pintype "passive"))
    )
    (net (code "23") (name "Net-(D2-PadANODE)") (class "Default")
      (node (ref "D2") (pin "ANODE") (pinfunction "ANODE_ANODE") (pintype "power_in"))
      (node (ref "R2") (pin "P$1") (pinfunction "P$1_P$1") (pintype "passive"))
    )
    (net (code "24") (name "Net-(J2-Pad1)") (class "Default")
      (node (ref "J2") (pin "1") (pinfunction "1_1") (pintype "passive"))
      (node (ref "R10") (pin "P$1") (pinfunction "P$1_P$1") (pintype "passive"))
    )
    (net (code "25") (name "Net-(Q1-G)") (class "Default")
      (node (ref "Q1") (pin "4") (pinfunction "G_4") (pintype "passive"))
      (node (ref "U4") (pin "2") (pinfunction "G_2") (pintype "bidirectional"))
    )
    (net (code "26") (name "Net-(Q2-G)") (class "Default")
      (node (ref "Q2") (pin "4") (pinfunction "G_4") (pintype "passive"))
      (node (ref "Q3") (pin "4") (pinfunction "G_4") (pintype "passive"))
      (node (ref "U5") (pin "2") (pinfunction "G_2") (pintype "bidirectional"))
    )
    (net (code "27") (name "Net-(U2-LX)") (class "Default")
      (node (ref "L1") (pin "P$1") (pinfunction "P$1_P$1") (pintype "passive"))
      (node (ref "U2") (pin "8") (pinfunction "LX_8") (pintype "passive"))
    )
    (net (code "28") (name "Net-(U2-VCC)") (class "Default")
      (node (ref "C9") (pin "P$1") (pinfunction "P$1_P$1") (pintype "passive"))
      (node (ref "U2") (pin "3") (pinfunction "VCC_3") (pintype "passive"))
    )
    (net (code "29") (name "VCC") (class "Default")
      (node (ref "C10") (pin "P$1") (pinfunction "P$1_P$1") (pintype "passive"))
      (node (ref "C11") (pin "P$1") (pinfunction "P$1_P$1") (pintype "passive"))
      (node (ref "C12") (pin "P$1") (pinfunction "P$1_P$1") (pintype "passive"))
      (node (ref "C13") (pin "P$1") (pinfunction "P$1_P$1") (pintype "passive"))
      (node (ref "C14") (pin "P$1") (pinfunction "P$1_P$1") (pintype "passive"))
      (node (ref "C15") (pin "P$1") (pinfunction "P$1_P$1") (pintype "passive"))
      (node (ref "C4") (pin "P$1") (pinfunction "P$1_P$1") (pintype "passive"))
      (node (ref "C7") (pin "P$1") (pinfunction "P$1_P$1") (pintype "passive"))
      (node (ref "D3V3") (pin "P$1") (pinfunction "P$1_P$1") (pintype "bidirectional"))
      (node (ref "J1") (pin "6") (pinfunction "6_6") (pintype "passive"))
      (node (ref "L1") (pin "P$2") (pinfunction "P$2_P$2") (pintype "passive"))
      (node (ref "R1") (pin "P$2") (pinfunction "P$2_P$2") (pintype "passive"))
      (node (ref "R10") (pin "P$2") (pinfunction "P$2_P$2") (pintype "passive"))
      (node (ref "R2") (pin "P$2") (pinfunction "P$2_P$2") (pintype "passive"))
      (node (ref "U2") (pin "4") (pinfunction "FB_4") (pintype "passive"))
      (node (ref "U3") (pin "20") (pinfunction "VREF+_20") (pintype "bidirectional"))
      (node (ref "U3") (pin "21") (pinfunction "VDDA_21") (pintype "bidirectional"))
      (node (ref "U3") (pin "23") (pinfunction "VDD_1_23") (pintype "bidirectional"))
      (node (ref "U3") (pin "35") (pinfunction "VDD_2_35") (pintype "bidirectional"))
      (node (ref "U3") (pin "48") (pinfunction "VDD_3_48") (pintype "bidirectional"))
      (node (ref "U6") (pin "3") (pinfunction "VCC_3") (pintype "power_in"))
    )
    (net (code "30") (name "unconnected-(J1-Pad1)") (class "Default")
      (node (ref "J1") (pin "1") (pinfunction "1_1") (pintype "passive"))
    )
    (net (code "31") (name "unconnected-(U2-MODE-Pad5)") (class "Default")
      (node (ref "U2") (pin "5") (pinfunction "MODE_5") (pintype "passive"))
    )
    (net (code "32") (name "unconnected-(U2-RESET-Pad6)") (class "Default")
      (node (ref "U2") (pin "6") (pinfunction "RESET_6") (pintype "passive"))
    )
    (net (code "33") (name "unconnected-(U3-PA4-Pad12)") (class "Default")
      (node (ref "U3") (pin "12") (pinfunction "PA4_12") (pintype "bidirectional"))
    )
    (net (code "34") (name "unconnected-(U3-PA5-Pad13)") (class "Default")
      (node (ref "U3") (pin "13") (pinfunction "PA5_13") (pintype "bidirectional"))
    )
    (net (code "35") (name "unconnected-(U3-PA6-Pad14)") (class "Default")
      (node (ref "U3") (pin "14") (pinfunction "PA6_14") (pintype "bidirectional"))
    )
    (net (code "36") (name "unconnected-(U3-PA7-Pad15)") (class "Default")
      (node (ref "U3") (pin "15") (pinfunction "PA7_15") (pintype "bidirectional"))
    )
    (net (code "37") (name "unconnected-(U3-PA13-Pad36)") (class "Default")
      (node (ref "U3") (pin "36") (pinfunction "PA13_36") (pintype "bidirectional"))
    )
    (net (code "38") (name "unconnected-(U3-PB0-Pad17)") (class "Default")
      (node (ref "U3") (pin "17") (pinfunction "PB0_17") (pintype "bidirectional"))
    )
    (net (code "39") (name "unconnected-(U3-PB1-Pad18)") (class "Default")
      (node (ref "U3") (pin "18") (pinfunction "PB1_18") (pintype "bidirectional"))
    )
    (net (code "40") (name "unconnected-(U3-PB2-Pad19)") (class "Default")
      (node (ref "U3") (pin "19") (pinfunction "PB2_19") (pintype "bidirectional"))
    )
    (net (code "41") (name "unconnected-(U3-PB3-Pad41)") (class "Default")
      (node (ref "U3") (pin "41") (pinfunction "PB3_41") (pintype "bidirectional"))
    )
    (net (code "42") (name "unconnected-(U3-PB4-Pad42)") (class "Default")
      (node (ref "U3") (pin "42") (pinfunction "PB4_42") (pintype "bidirectional"))
    )
    (net (code "43") (name "unconnected-(U3-PB5-Pad43)") (class "Default")
      (node (ref "U3") (pin "43") (pinfunction "PB5_43") (pintype "bidirectional"))
    )
    (net (code "44") (name "unconnected-(U3-PB6-Pad44)") (class "Default")
      (node (ref "U3") (pin "44") (pinfunction "PB6_44") (pintype "bidirectional"))
    )
    (net (code "45") (name "unconnected-(U3-PB7-Pad45)") (class "Default")
      (node (ref "U3") (pin "45") (pinfunction "PB7_45") (pintype "bidirectional"))
    )
    (net (code "46") (name "unconnected-(U3-PB8-BOOT0-Pad46)") (class "Default")
      (node (ref "U3") (pin "46") (pinfunction "PB8-BOOT0_46") (pintype "bidirectional"))
    )
    (net (code "47") (name "unconnected-(U3-PB9-Pad47)") (class "Default")
      (node (ref "U3") (pin "47") (pinfunction "PB9_47") (pintype "bidirectional"))
    )
    (net (code "48") (name "unconnected-(U3-PB10-Pad22)") (class "Default")
      (node (ref "U3") (pin "22") (pinfunction "PB10_22") (pintype "bidirectional"))
    )
    (net (code "49") (name "unconnected-(U3-PB11-Pad24)") (class "Default")
      (node (ref "U3") (pin "24") (pinfunction "PB11_24") (pintype "bidirectional"))
    )
    (net (code "50") (name "unconnected-(U3-PB12-Pad25)") (class "Default")
      (node (ref "U3") (pin "25") (pinfunction "PB12_25") (pintype "bidirectional"))
    )
    (net (code "51") (name "unconnected-(U3-PB13-Pad26)") (class "Default")
      (node (ref "U3") (pin "26") (pinfunction "PB13_26") (pintype "bidirectional"))
    )
    (net (code "52") (name "unconnected-(U3-PB14-Pad27)") (class "Default")
      (node (ref "U3") (pin "27") (pinfunction "PB14_27") (pintype "bidirectional"))
    )
    (net (code "53") (name "unconnected-(U3-PB15-Pad28)") (class "Default")
      (node (ref "U3") (pin "28") (pinfunction "PB15_28") (pintype "bidirectional"))
    )
    (net (code "54") (name "unconnected-(U3-PC4-Pad16)") (class "Default")
      (node (ref "U3") (pin "16") (pinfunction "PC4_16") (pintype "bidirectional"))
    )
    (net (code "55") (name "unconnected-(U3-PC6-Pad29)") (class "Default")
      (node (ref "U3") (pin "29") (pinfunction "PC6_29") (pintype "bidirectional"))
    )
    (net (code "56") (name "unconnected-(U3-PC10-Pad39)") (class "Default")
      (node (ref "U3") (pin "39") (pinfunction "PC10_39") (pintype "bidirectional"))
    )
    (net (code "57") (name "unconnected-(U3-PC11-Pad40)") (class "Default")
      (node (ref "U3") (pin "40") (pinfunction "PC11_40") (pintype "bidirectional"))
    )
    (net (code "58") (name "unconnected-(U3-PC13-Pad2)") (class "Default")
      (node (ref "U3") (pin "2") (pinfunction "PC13_2") (pintype "bidirectional"))
    )
    (net (code "59") (name "unconnected-(U3-PF0-OSC_IN-Pad5)") (class "Default")
      (node (ref "U3") (pin "5") (pinfunction "PF0-OSC_IN_5") (pintype "bidirectional"))
    )
    (net (code "60") (name "unconnected-(U3-PF1-OSC_OUT-Pad6)") (class "Default")
      (node (ref "U3") (pin "6") (pinfunction "PF1-OSC_OUT_6") (pintype "bidirectional"))
    )
    (net (code "61") (name "unconnected-(U3-VBAT-Pad1)") (class "Default")
      (node (ref "U3") (pin "1") (pinfunction "VBAT_1") (pintype "bidirectional"))
    )
  )
)
